# Sheet1.net
KiCad netlist of a schematic drawn in Altium Designer
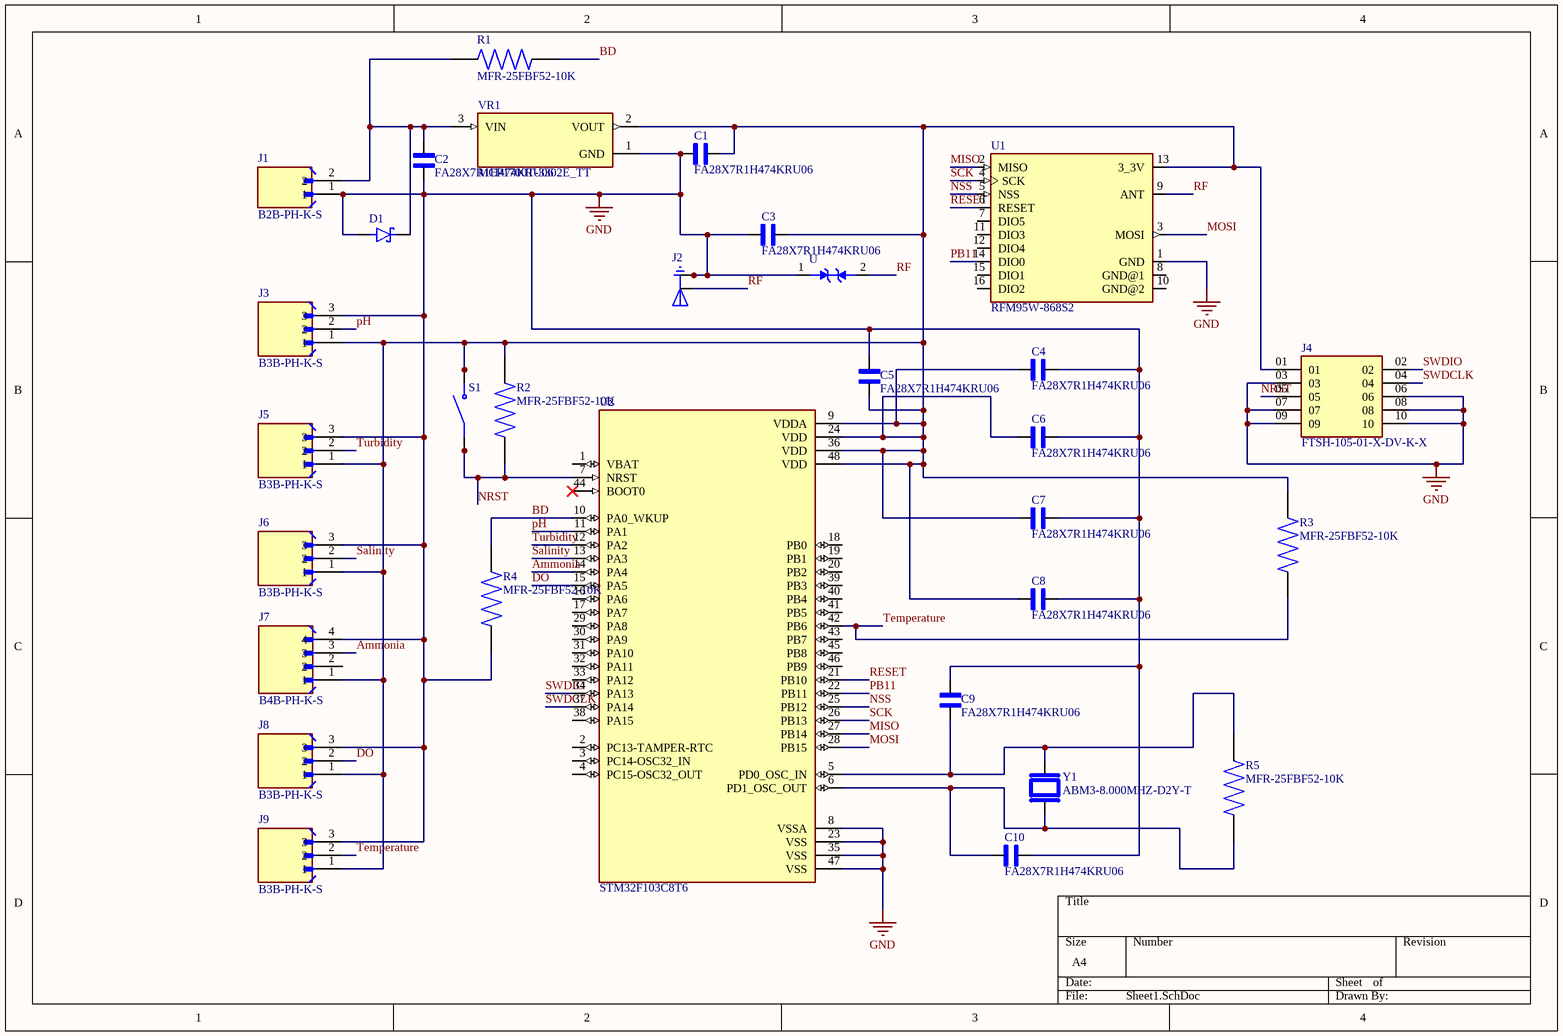
[diagram p0: Sheet1.SchDoc]

(export (version "E")
  (design (tool "Eeschema 10.0.6"))
  (components
    (comp (ref "C1")
      (value "FA28X7R1H474KRU06")
      (footprint "CAPRB500W50L400T250H550")
      (description "0.47 ÂµF Â±10% 50V Ceramic Capacitor X7R Radial")
      (fields (field (name "MF") "TDK"))
      (libsource (lib "Schlib1") (part "FA28X7R1H474KRU06"))
    )
    (comp (ref "C2")
      (value "FA28X7R1H474KRU06")
      (footprint "CAPRB500W50L400T250H550")
      (description "0.47 ÂµF Â±10% 50V Ceramic Capacitor X7R Radial")
      (fields (field (name "MF") "TDK"))
      (libsource (lib "") (part "FA28X7R1H474KRU06_1"))
    )
    (comp (ref "C3")
      (value "FA28X7R1H474KRU06")
      (footprint "CAPRB500W50L400T250H550")
      (description "0.47 ÂµF Â±10% 50V Ceramic Capacitor X7R Radial")
      (fields (field (name "MF") "TDK"))
      (libsource (lib "Schlib1") (part "FA28X7R1H474KRU06"))
    )
    (comp (ref "C4")
      (value "FA28X7R1H474KRU06")
      (footprint "CAPRB500W50L400T250H550")
      (description "0.47 ÂµF Â±10% 50V Ceramic Capacitor X7R Radial")
      (fields (field (name "MF") "TDK"))
      (libsource (lib "Schlib1") (part "FA28X7R1H474KRU06"))
    )
    (comp (ref "C5")
      (value "FA28X7R1H474KRU06")
      (footprint "CAPRB500W50L400T250H550")
      (description "0.47 ÂµF Â±10% 50V Ceramic Capacitor X7R Radial")
      (fields (field (name "MF") "TDK"))
      (libsource (lib "") (part "FA28X7R1H474KRU06_1"))
    )
    (comp (ref "C6")
      (value "FA28X7R1H474KRU06")
      (footprint "CAPRB500W50L400T250H550")
      (description "0.47 ÂµF Â±10% 50V Ceramic Capacitor X7R Radial")
      (fields (field (name "MF") "TDK"))
      (libsource (lib "Schlib1") (part "FA28X7R1H474KRU06"))
    )
    (comp (ref "C7")
      (value "FA28X7R1H474KRU06")
      (footprint "CAPRB500W50L400T250H550")
      (description "0.47 ÂµF Â±10% 50V Ceramic Capacitor X7R Radial")
      (fields (field (name "MF") "TDK"))
      (libsource (lib "Schlib1") (part "FA28X7R1H474KRU06"))
    )
    (comp (ref "C8")
      (value "FA28X7R1H474KRU06")
      (footprint "CAPRB500W50L400T250H550")
      (description "0.47 ÂµF Â±10% 50V Ceramic Capacitor X7R Radial")
      (fields (field (name "MF") "TDK"))
      (libsource (lib "Schlib1") (part "FA28X7R1H474KRU06"))
    )
    (comp (ref "C9")
      (value "FA28X7R1H474KRU06")
      (footprint "CAPRB500W50L400T250H550")
      (description "0.47 ÂµF Â±10% 50V Ceramic Capacitor X7R Radial")
      (fields (field (name "MF") "TDK"))
      (libsource (lib "") (part "FA28X7R1H474KRU06_1"))
    )
    (comp (ref "C10")
      (value "FA28X7R1H474KRU06")
      (footprint "CAPRB500W50L400T250H550")
      (description "0.47 ÂµF Â±10% 50V Ceramic Capacitor X7R Radial")
      (fields (field (name "MF") "TDK"))
      (libsource (lib "Schlib1") (part "FA28X7R1H474KRU06"))
    )
    (comp (ref "D1")
      (value "SS14")
      (footprint "DIOM4325X250N")
      (description "1A, 40V, Schottky Rectifier")
      (fields (field (name "MF") "Taiwan Semiconductor"))
      (libsource (lib "Schlib1") (part "SS14"))
    )
    (comp (ref "J1")
      (value "B2B-PH-K-S")
      (footprint "JST_B2B-PH-K-S")
      (description "Connector Header Through Hole 2 position 0.079 (2.00mm)")
      (fields (field (name "MF") "JST Sales America Inc."))
      (libsource (lib "Schlib1") (part "B2B-PH-K-S"))
    )
    (comp (ref "J2")
      (value "U.FL-R-SMT-1(10)")
      (footprint "HRS_U.FL-R-SMT-1(10)")
      (description "U.FL Series 6 Ghz 50 Ohm Ultra-small SMT Coaxial Cable Receptacle")
      (libsource (lib "Schlib1") (part "U.FL-R-SMT-1(10)"))
    )
    (comp (ref "J3")
      (value "B3B-PH-K-S")
      (footprint "JST_B3B-PH-K-S")
      (fields (field (name "MF") "{'manufacturer': u'JST Sales America Inc.'}"))
      (libsource (lib "Schlib1") (part "B3B-PH-K-S"))
    )
    (comp (ref "J4")
      (value "FTSH-105-01-X-DV-K-X")
      (footprint "SAMTEC_FTSH-105-01-X-DV-K-X")
      (fields (field (name "MF") "{'manufacturer': u'Samtec Inc.'}"))
      (libsource (lib "Schlib1") (part "FTSH-105-01-X-DV-K-X"))
    )
    (comp (ref "J5")
      (value "B3B-PH-K-S")
      (footprint "JST_B3B-PH-K-S")
      (fields (field (name "MF") "{'manufacturer': u'JST Sales America Inc.'}"))
      (libsource (lib "Schlib1") (part "B3B-PH-K-S"))
    )
    (comp (ref "J6")
      (value "B3B-PH-K-S")
      (footprint "JST_B3B-PH-K-S")
      (fields (field (name "MF") "{'manufacturer': u'JST Sales America Inc.'}"))
      (libsource (lib "Schlib1") (part "B3B-PH-K-S"))
    )
    (comp (ref "J7")
      (value "B4B-PH-K-S")
      (footprint "JST_B4B-PH-K-S")
      (fields (field (name "MF") "{'manufacturer': u'JST Sales America Inc.'}"))
      (libsource (lib "Schlib1") (part "B4B-PH-K-S"))
    )
    (comp (ref "J8")
      (value "B3B-PH-K-S")
      (footprint "JST_B3B-PH-K-S")
      (fields (field (name "MF") "{'manufacturer': u'JST Sales America Inc.'}"))
      (libsource (lib "Schlib1") (part "B3B-PH-K-S"))
    )
    (comp (ref "J9")
      (value "B3B-PH-K-S")
      (footprint "JST_B3B-PH-K-S")
      (fields (field (name "MF") "{'manufacturer': u'JST Sales America Inc.'}"))
      (libsource (lib "Schlib1") (part "B3B-PH-K-S"))
    )
    (comp (ref "R1")
      (value "MFR-25FBF52-10K")
      (footprint "RESAD1100W55L680D260")
      (description "10.2 kOhms Â±1% 0.25W, 1/4W Through Hole Resistor Axial - Metal Film")
      (fields (field (name "MF") "Yageo"))
      (libsource (lib "Schlib1") (part "MFR-25FBF52-10K"))
    )
    (comp (ref "R2")
      (value "MFR-25FBF52-10K")
      (footprint "RESAD1100W55L680D260")
      (description "10.2 kOhms Â±1% 0.25W, 1/4W Through Hole Resistor Axial - Metal Film")
      (fields (field (name "MF") "Yageo"))
      (libsource (lib "Schlib1") (part "MFR-25FBF52-10K"))
    )
    (comp (ref "R3")
      (value "MFR-25FBF52-10K")
      (footprint "RESAD1100W55L680D260")
      (description "10.2 kOhms Â±1% 0.25W, 1/4W Through Hole Resistor Axial - Metal Film")
      (fields (field (name "MF") "Yageo"))
      (libsource (lib "Schlib1") (part "MFR-25FBF52-10K"))
    )
    (comp (ref "R4")
      (value "MFR-25FBF52-10K")
      (footprint "RESAD1100W55L680D260")
      (description "10.2 kOhms Â±1% 0.25W, 1/4W Through Hole Resistor Axial - Metal Film")
      (fields (field (name "MF") "Yageo"))
      (libsource (lib "Schlib1") (part "MFR-25FBF52-10K"))
    )
    (comp (ref "R5")
      (value "MFR-25FBF52-10K")
      (footprint "RESAD1100W55L680D260")
      (description "10.2 kOhms Â±1% 0.25W, 1/4W Through Hole Resistor Axial - Metal Film")
      (fields (field (name "MF") "Yageo"))
      (libsource (lib "Schlib1") (part "MFR-25FBF52-10K"))
    )
    (comp (ref "S1")
      (value "TS-1187A-B-A-B")
      (footprint "SW_TS-1187A-B-A-B")
      (description "SPST 50mA @ 12VDC Top Actuated Round Button 160gf SMD Tactile Switches RoHS")
      (libsource (lib "Schlib1") (part "TS-1187A-B-A-B"))
    )
    (comp (ref "U")
      (value "ESD9B5.0ST5G")
      (footprint "SODFL1006X40N")
      (description "Clamp Ipp Tvs Diode Surface Mount SOD-923")
      (fields (field (name "MF") "ON Semiconductor"))
      (libsource (lib "Schlib1") (part "ESD9B5.0ST5G"))
    )
    (comp (ref "U1")
      (value "RFM95W-868S2")
      (footprint "XCVR_RFM95W-868S2")
      (description "General ISM < 1GHz LoRaâ„¢ Transceiver Module 868MHz Antenna Not Included Surface Mount")
      (fields (field (name "MF") "RF"))
      (libsource (lib "Schlib1") (part "RFM95W-868S2"))
    )
    (comp (ref "U2")
      (value "STM32F103C8T6")
      (footprint "QFP50P900X900X160-48N")
      (description "ARM® Cortex®-M3 STM32F1 Microcontroller IC 32-Bit 72MHz 64KB (64K x 8) FLASH 48-LQFP (7x7)")
      (fields (field (name "MF") "STMicroelectronics"))
      (libsource (lib "Schlib1") (part "STM32F103C8T6"))
    )
    (comp (ref "VR1")
      (value "MCP1700T-3302E_TT")
      (footprint "SOT95P237X112-3N")
      (fields (field (name "MF") "Microchip") (field (name "MP") "MCP1700T-3302E/TT"))
      (libsource (lib "Schlib1") (part "MCP1700T-3302E_TT"))
    )
    (comp (ref "Y1")
      (value "ABM3-8.000MHZ-D2Y-T")
      (footprint "XTAL_ABM3-8.000MHZ-D2Y-T")
      (description "8 MHz Â±20ppm Crystal 18pF 140 Ohms 2-SMD, No Lead")
      (fields (field (name "MF") "Abracon"))
      (libsource (lib "Schlib1") (part "ABM3-8.000MHZ-D2Y-T"))
    )
  )
  (nets
    (net (code "1") (name "/Ammonia") (class "Default")
      (node (ref "J7") (pin "3") (pinfunction "3_3") (pintype "passive"))
      (node (ref "U2") (pin "14") (pinfunction "PA4_14") (pintype "bidirectional"))
    )
    (net (code "2") (name "/BD") (class "Default")
      (node (ref "R1") (pin "2") (pinfunction "2_2") (pintype "passive"))
      (node (ref "R4") (pin "2") (pinfunction "2_2") (pintype "passive"))
      (node (ref "U2") (pin "10") (pinfunction "PA0_WKUP_10") (pintype "bidirectional"))
    )
    (net (code "3") (name "/DO") (class "Default")
      (node (ref "J8") (pin "2") (pinfunction "2_2") (pintype "passive"))
      (node (ref "U2") (pin "15") (pinfunction "PA5_15") (pintype "bidirectional"))
    )
    (net (code "4") (name "/MISO") (class "Default")
      (node (ref "U1") (pin "2") (pinfunction "MISO_2") (pintype "input"))
      (node (ref "U2") (pin "27") (pinfunction "PB14_27") (pintype "bidirectional"))
    )
    (net (code "5") (name "/MOSI") (class "Default")
      (node (ref "U1") (pin "3") (pinfunction "MOSI_3") (pintype "output"))
      (node (ref "U2") (pin "28") (pinfunction "PB15_28") (pintype "bidirectional"))
    )
    (net (code "6") (name "/NRST") (class "Default")
      (node (ref "J4") (pin "05") (pinfunction "05_05") (pintype "passive"))
      (node (ref "R2") (pin "1") (pinfunction "1_1") (pintype "passive"))
      (node (ref "S1") (pin "A") (pinfunction "COM_A") (pintype "passive"))
      (node (ref "S1") (pin "B") (pinfunction "COM_B") (pintype "passive"))
      (node (ref "U2") (pin "7") (pinfunction "NRST_7") (pintype "input"))
    )
    (net (code "7") (name "/NSS") (class "Default")
      (node (ref "U1") (pin "5") (pinfunction "NSS_5") (pintype "input"))
      (node (ref "U2") (pin "25") (pinfunction "PB12_25") (pintype "bidirectional"))
    )
    (net (code "8") (name "/PB11") (class "Default")
      (node (ref "U1") (pin "14") (pinfunction "DIO0_14") (pintype "bidirectional"))
      (node (ref "U2") (pin "22") (pinfunction "PB11_22") (pintype "bidirectional"))
    )
    (net (code "9") (name "/RESET") (class "Default")
      (node (ref "U1") (pin "6") (pinfunction "RESET_6") (pintype "bidirectional"))
      (node (ref "U2") (pin "21") (pinfunction "PB10_21") (pintype "bidirectional"))
    )
    (net (code "10") (name "/RF") (class "Default")
      (node (ref "J2") (pin "2") (pinfunction "SIG_2") (pintype "passive"))
      (node (ref "U") (pin "2") (pinfunction "A1_2") (pintype "passive"))
      (node (ref "U1") (pin "9") (pinfunction "ANT_9") (pintype "passive"))
    )
    (net (code "11") (name "/SCK") (class "Default")
      (node (ref "U1") (pin "4") (pinfunction "SCK_4") (pintype "input"))
      (node (ref "U2") (pin "26") (pinfunction "PB13_26") (pintype "bidirectional"))
    )
    (net (code "12") (name "/SWDCLK") (class "Default")
      (node (ref "J4") (pin "04") (pinfunction "04_04") (pintype "passive"))
      (node (ref "U2") (pin "37") (pinfunction "PA14_37") (pintype "bidirectional"))
    )
    (net (code "13") (name "/SWDIO") (class "Default")
      (node (ref "J4") (pin "02") (pinfunction "02_02") (pintype "passive"))
      (node (ref "U2") (pin "34") (pinfunction "PA13_34") (pintype "bidirectional"))
    )
    (net (code "14") (name "/Salinity") (class "Default")
      (node (ref "J6") (pin "2") (pinfunction "2_2") (pintype "passive"))
      (node (ref "U2") (pin "13") (pinfunction "PA3_13") (pintype "bidirectional"))
    )
    (net (code "15") (name "/Temperature") (class "Default")
      (node (ref "J9") (pin "2") (pinfunction "2_2") (pintype "passive"))
      (node (ref "R3") (pin "1") (pinfunction "1_1") (pintype "passive"))
      (node (ref "U2") (pin "42") (pinfunction "PB6_42") (pintype "bidirectional"))
    )
    (net (code "16") (name "/Turbidity") (class "Default")
      (node (ref "J5") (pin "2") (pinfunction "2_2") (pintype "passive"))
      (node (ref "U2") (pin "12") (pinfunction "PA2_12") (pintype "bidirectional"))
    )
    (net (code "17") (name "/pH") (class "Default")
      (node (ref "J3") (pin "2") (pinfunction "2_2") (pintype "passive"))
      (node (ref "U2") (pin "11") (pinfunction "PA1_11") (pintype "bidirectional"))
    )
    (net (code "18") (name "GND") (class "Default")
      (node (ref "C1") (pin "1") (pinfunction "1_1") (pintype "passive"))
      (node (ref "C10") (pin "2") (pinfunction "2_2") (pintype "passive"))
      (node (ref "C2") (pin "1") (pinfunction "1_1") (pintype "passive"))
      (node (ref "C3") (pin "1") (pinfunction "1_1") (pintype "passive"))
      (node (ref "C4") (pin "2") (pinfunction "2_2") (pintype "passive"))
      (node (ref "C5") (pin "2") (pinfunction "2_2") (pintype "passive"))
      (node (ref "C6") (pin "2") (pinfunction "2_2") (pintype "passive"))
      (node (ref "C7") (pin "2") (pinfunction "2_2") (pintype "passive"))
      (node (ref "C8") (pin "2") (pinfunction "2_2") (pintype "passive"))
      (node (ref "C9") (pin "2") (pinfunction "2_2") (pintype "passive"))
      (node (ref "D1") (pin "A") (pinfunction "A_A") (pintype "passive"))
      (node (ref "J1") (pin "1") (pinfunction "1_1") (pintype "passive"))
      (node (ref "J2") (pin "1") (pinfunction "GND_1") (pintype "passive"))
      (node (ref "J2") (pin "3") (pinfunction "GND_3") (pintype "passive"))
      (node (ref "J3") (pin "3") (pinfunction "3_3") (pintype "passive"))
      (node (ref "J4") (pin "03") (pinfunction "03_03") (pintype "passive"))
      (node (ref "J4") (pin "06") (pinfunction "06_06") (pintype "passive"))
      (node (ref "J4") (pin "07") (pinfunction "07_07") (pintype "passive"))
      (node (ref "J4") (pin "08") (pinfunction "08_08") (pintype "passive"))
      (node (ref "J4") (pin "09") (pinfunction "09_09") (pintype "passive"))
      (node (ref "J4") (pin "10") (pinfunction "10_10") (pintype "passive"))
      (node (ref "J5") (pin "3") (pinfunction "3_3") (pintype "passive"))
      (node (ref "J6") (pin "3") (pinfunction "3_3") (pintype "passive"))
      (node (ref "J7") (pin "4") (pinfunction "4_4") (pintype "passive"))
      (node (ref "J8") (pin "3") (pinfunction "3_3") (pintype "passive"))
      (node (ref "J9") (pin "3") (pinfunction "3_3") (pintype "passive"))
      (node (ref "R4") (pin "1") (pinfunction "1_1") (pintype "passive"))
      (node (ref "U") (pin "1") (pinfunction "A_1") (pintype "passive"))
      (node (ref "U1") (pin "1") (pinfunction "GND_1") (pintype "power_in"))
      (node (ref "U2") (pin "23") (pinfunction "VSS_23") (pintype "power_in"))
      (node (ref "U2") (pin "35") (pinfunction "VSS_35") (pintype "power_in"))
      (node (ref "U2") (pin "47") (pinfunction "VSS_47") (pintype "power_in"))
      (node (ref "U2") (pin "8") (pinfunction "VSSA_8") (pintype "power_in"))
      (node (ref "VR1") (pin "1") (pinfunction "GND_1") (pintype "power_in"))
    )
    (net (code "19") (name "Net-(D1-K)") (class "Default")
      (node (ref "C2") (pin "2") (pinfunction "2_2") (pintype "passive"))
      (node (ref "D1") (pin "C") (pinfunction "K_C") (pintype "passive"))
      (node (ref "J1") (pin "2") (pinfunction "2_2") (pintype "passive"))
      (node (ref "R1") (pin "1") (pinfunction "1_1") (pintype "passive"))
      (node (ref "VR1") (pin "3") (pinfunction "VIN_3") (pintype "input"))
    )
    (net (code "20") (name "Net-(U1-3_3V)") (class "Default")
      (node (ref "C1") (pin "2") (pinfunction "2_2") (pintype "passive"))
      (node (ref "C3") (pin "2") (pinfunction "2_2") (pintype "passive"))
      (node (ref "C4") (pin "1") (pinfunction "1_1") (pintype "passive"))
      (node (ref "C5") (pin "1") (pinfunction "1_1") (pintype "passive"))
      (node (ref "C6") (pin "1") (pinfunction "1_1") (pintype "passive"))
      (node (ref "C7") (pin "1") (pinfunction "1_1") (pintype "passive"))
      (node (ref "C8") (pin "1") (pinfunction "1_1") (pintype "passive"))
      (node (ref "J3") (pin "1") (pinfunction "1_1") (pintype "passive"))
      (node (ref "J4") (pin "01") (pinfunction "01_01") (pintype "passive"))
      (node (ref "J5") (pin "1") (pinfunction "1_1") (pintype "passive"))
      (node (ref "J6") (pin "1") (pinfunction "1_1") (pintype "passive"))
      (node (ref "J7") (pin "1") (pinfunction "1_1") (pintype "passive"))
      (node (ref "J8") (pin "1") (pinfunction "1_1") (pintype "passive"))
      (node (ref "J9") (pin "1") (pinfunction "1_1") (pintype "passive"))
      (node (ref "R2") (pin "2") (pinfunction "2_2") (pintype "passive"))
      (node (ref "R3") (pin "2") (pinfunction "2_2") (pintype "passive"))
      (node (ref "S1") (pin "C") (pinfunction "NO_C") (pintype "passive"))
      (node (ref "S1") (pin "D") (pinfunction "NO_D") (pintype "passive"))
      (node (ref "U1") (pin "13") (pinfunction "3_3V_13") (pintype "power_in"))
      (node (ref "U2") (pin "24") (pinfunction "VDD_24") (pintype "power_in"))
      (node (ref "U2") (pin "36") (pinfunction "VDD_36") (pintype "power_in"))
      (node (ref "U2") (pin "48") (pinfunction "VDD_48") (pintype "power_in"))
      (node (ref "U2") (pin "9") (pinfunction "VDDA_9") (pintype "power_in"))
      (node (ref "VR1") (pin "2") (pinfunction "VOUT_2") (pintype "output"))
    )
    (net (code "21") (name "Net-(U2-PD0_OSC_IN)") (class "Default")
      (node (ref "C9") (pin "1") (pinfunction "1_1") (pintype "passive"))
      (node (ref "R5") (pin "2") (pinfunction "2_2") (pintype "passive"))
      (node (ref "U2") (pin "5") (pinfunction "PD0_OSC_IN_5") (pintype "bidirectional"))
      (node (ref "Y1") (pin "1") (pinfunction "1_1") (pintype "passive"))
    )
    (net (code "22") (name "Net-(U2-PD1_OSC_OUT)") (class "Default")
      (node (ref "C10") (pin "1") (pinfunction "1_1") (pintype "passive"))
      (node (ref "R5") (pin "1") (pinfunction "1_1") (pintype "passive"))
      (node (ref "U2") (pin "6") (pinfunction "PD1_OSC_OUT_6") (pintype "bidirectional"))
      (node (ref "Y1") (pin "2") (pinfunction "2_2") (pintype "passive"))
    )
    (net (code "23") (name "unconnected-(J7-Pad2)") (class "Default")
      (node (ref "J7") (pin "2") (pinfunction "2_2") (pintype "passive"))
    )
    (net (code "24") (name "unconnected-(U1-DIO1-Pad15)") (class "Default")
      (node (ref "U1") (pin "15") (pinfunction "DIO1_15") (pintype "bidirectional"))
    )
    (net (code "25") (name "unconnected-(U1-DIO2-Pad16)") (class "Default")
      (node (ref "U1") (pin "16") (pinfunction "DIO2_16") (pintype "bidirectional"))
    )
    (net (code "26") (name "unconnected-(U1-DIO3-Pad11)") (class "Default")
      (node (ref "U1") (pin "11") (pinfunction "DIO3_11") (pintype "bidirectional"))
    )
    (net (code "27") (name "unconnected-(U1-DIO4-Pad12)") (class "Default")
      (node (ref "U1") (pin "12") (pinfunction "DIO4_12") (pintype "bidirectional"))
    )
    (net (code "28") (name "unconnected-(U1-DIO5-Pad7)") (class "Default")
      (node (ref "U1") (pin "7") (pinfunction "DIO5_7") (pintype "bidirectional"))
    )
    (net (code "29") (name "unconnected-(U1-GND@1-Pad8)") (class "Default")
      (node (ref "U1") (pin "8") (pinfunction "GND@1_8") (pintype "power_in"))
    )
    (net (code "30") (name "unconnected-(U1-GND@2-Pad10)") (class "Default")
      (node (ref "U1") (pin "10") (pinfunction "GND@2_10") (pintype "power_in"))
    )
    (net (code "31") (name "unconnected-(U2-BOOT0-Pad44)") (class "Default")
      (node (ref "U2") (pin "44") (pinfunction "BOOT0_44") (pintype "input+no_connect"))
    )
    (net (code "32") (name "unconnected-(U2-PA6-Pad16)") (class "Default")
      (node (ref "U2") (pin "16") (pinfunction "PA6_16") (pintype "bidirectional"))
    )
    (net (code "33") (name "unconnected-(U2-PA7-Pad17)") (class "Default")
      (node (ref "U2") (pin "17") (pinfunction "PA7_17") (pintype "bidirectional"))
    )
    (net (code "34") (name "unconnected-(U2-PA8-Pad29)") (class "Default")
      (node (ref "U2") (pin "29") (pinfunction "PA8_29") (pintype "bidirectional"))
    )
    (net (code "35") (name "unconnected-(U2-PA9-Pad30)") (class "Default")
      (node (ref "U2") (pin "30") (pinfunction "PA9_30") (pintype "bidirectional"))
    )
    (net (code "36") (name "unconnected-(U2-PA10-Pad31)") (class "Default")
      (node (ref "U2") (pin "31") (pinfunction "PA10_31") (pintype "bidirectional"))
    )
    (net (code "37") (name "unconnected-(U2-PA11-Pad32)") (class "Default")
      (node (ref "U2") (pin "32") (pinfunction "PA11_32") (pintype "bidirectional"))
    )
    (net (code "38") (name "unconnected-(U2-PA12-Pad33)") (class "Default")
      (node (ref "U2") (pin "33") (pinfunction "PA12_33") (pintype "bidirectional"))
    )
    (net (code "39") (name "unconnected-(U2-PA15-Pad38)") (class "Default")
      (node (ref "U2") (pin "38") (pinfunction "PA15_38") (pintype "bidirectional"))
    )
    (net (code "40") (name "unconnected-(U2-PB0-Pad18)") (class "Default")
      (node (ref "U2") (pin "18") (pinfunction "PB0_18") (pintype "bidirectional"))
    )
    (net (code "41") (name "unconnected-(U2-PB1-Pad19)") (class "Default")
      (node (ref "U2") (pin "19") (pinfunction "PB1_19") (pintype "bidirectional"))
    )
    (net (code "42") (name "unconnected-(U2-PB2-Pad20)") (class "Default")
      (node (ref "U2") (pin "20") (pinfunction "PB2_20") (pintype "bidirectional"))
    )
    (net (code "43") (name "unconnected-(U2-PB3-Pad39)") (class "Default")
      (node (ref "U2") (pin "39") (pinfunction "PB3_39") (pintype "bidirectional"))
    )
    (net (code "44") (name "unconnected-(U2-PB4-Pad40)") (class "Default")
      (node (ref "U2") (pin "40") (pinfunction "PB4_40") (pintype "bidirectional"))
    )
    (net (code "45") (name "unconnected-(U2-PB5-Pad41)") (class "Default")
      (node (ref "U2") (pin "41") (pinfunction "PB5_41") (pintype "bidirectional"))
    )
    (net (code "46") (name "unconnected-(U2-PB7-Pad43)") (class "Default")
      (node (ref "U2") (pin "43") (pinfunction "PB7_43") (pintype "bidirectional"))
    )
    (net (code "47") (name "unconnected-(U2-PB8-Pad45)") (class "Default")
      (node (ref "U2") (pin "45") (pinfunction "PB8_45") (pintype "bidirectional"))
    )
    (net (code "48") (name "unconnected-(U2-PB9-Pad46)") (class "Default")
      (node (ref "U2") (pin "46") (pinfunction "PB9_46") (pintype "bidirectional"))
    )
    (net (code "49") (name "unconnected-(U2-PC13-TAMPER-RTC-Pad2)") (class "Default")
      (node (ref "U2") (pin "2") (pinfunction "PC13-TAMPER-RTC_2") (pintype "bidirectional"))
    )
    (net (code "50") (name "unconnected-(U2-PC14-OSC32_IN-Pad3)") (class "Default")
      (node (ref "U2") (pin "3") (pinfunction "PC14-OSC32_IN_3") (pintype "bidirectional"))
    )
    (net (code "51") (name "unconnected-(U2-PC15-OSC32_OUT-Pad4)") (class "Default")
      (node (ref "U2") (pin "4") (pinfunction "PC15-OSC32_OUT_4") (pintype "bidirectional"))
    )
    (net (code "52") (name "unconnected-(U2-VBAT-Pad1)") (class "Default")
      (node (ref "U2") (pin "1") (pinfunction "VBAT_1") (pintype "bidirectional"))
    )
  )
)
